# WizFiShield.net
KiCad netlist of a schematic drawn in EAGLE
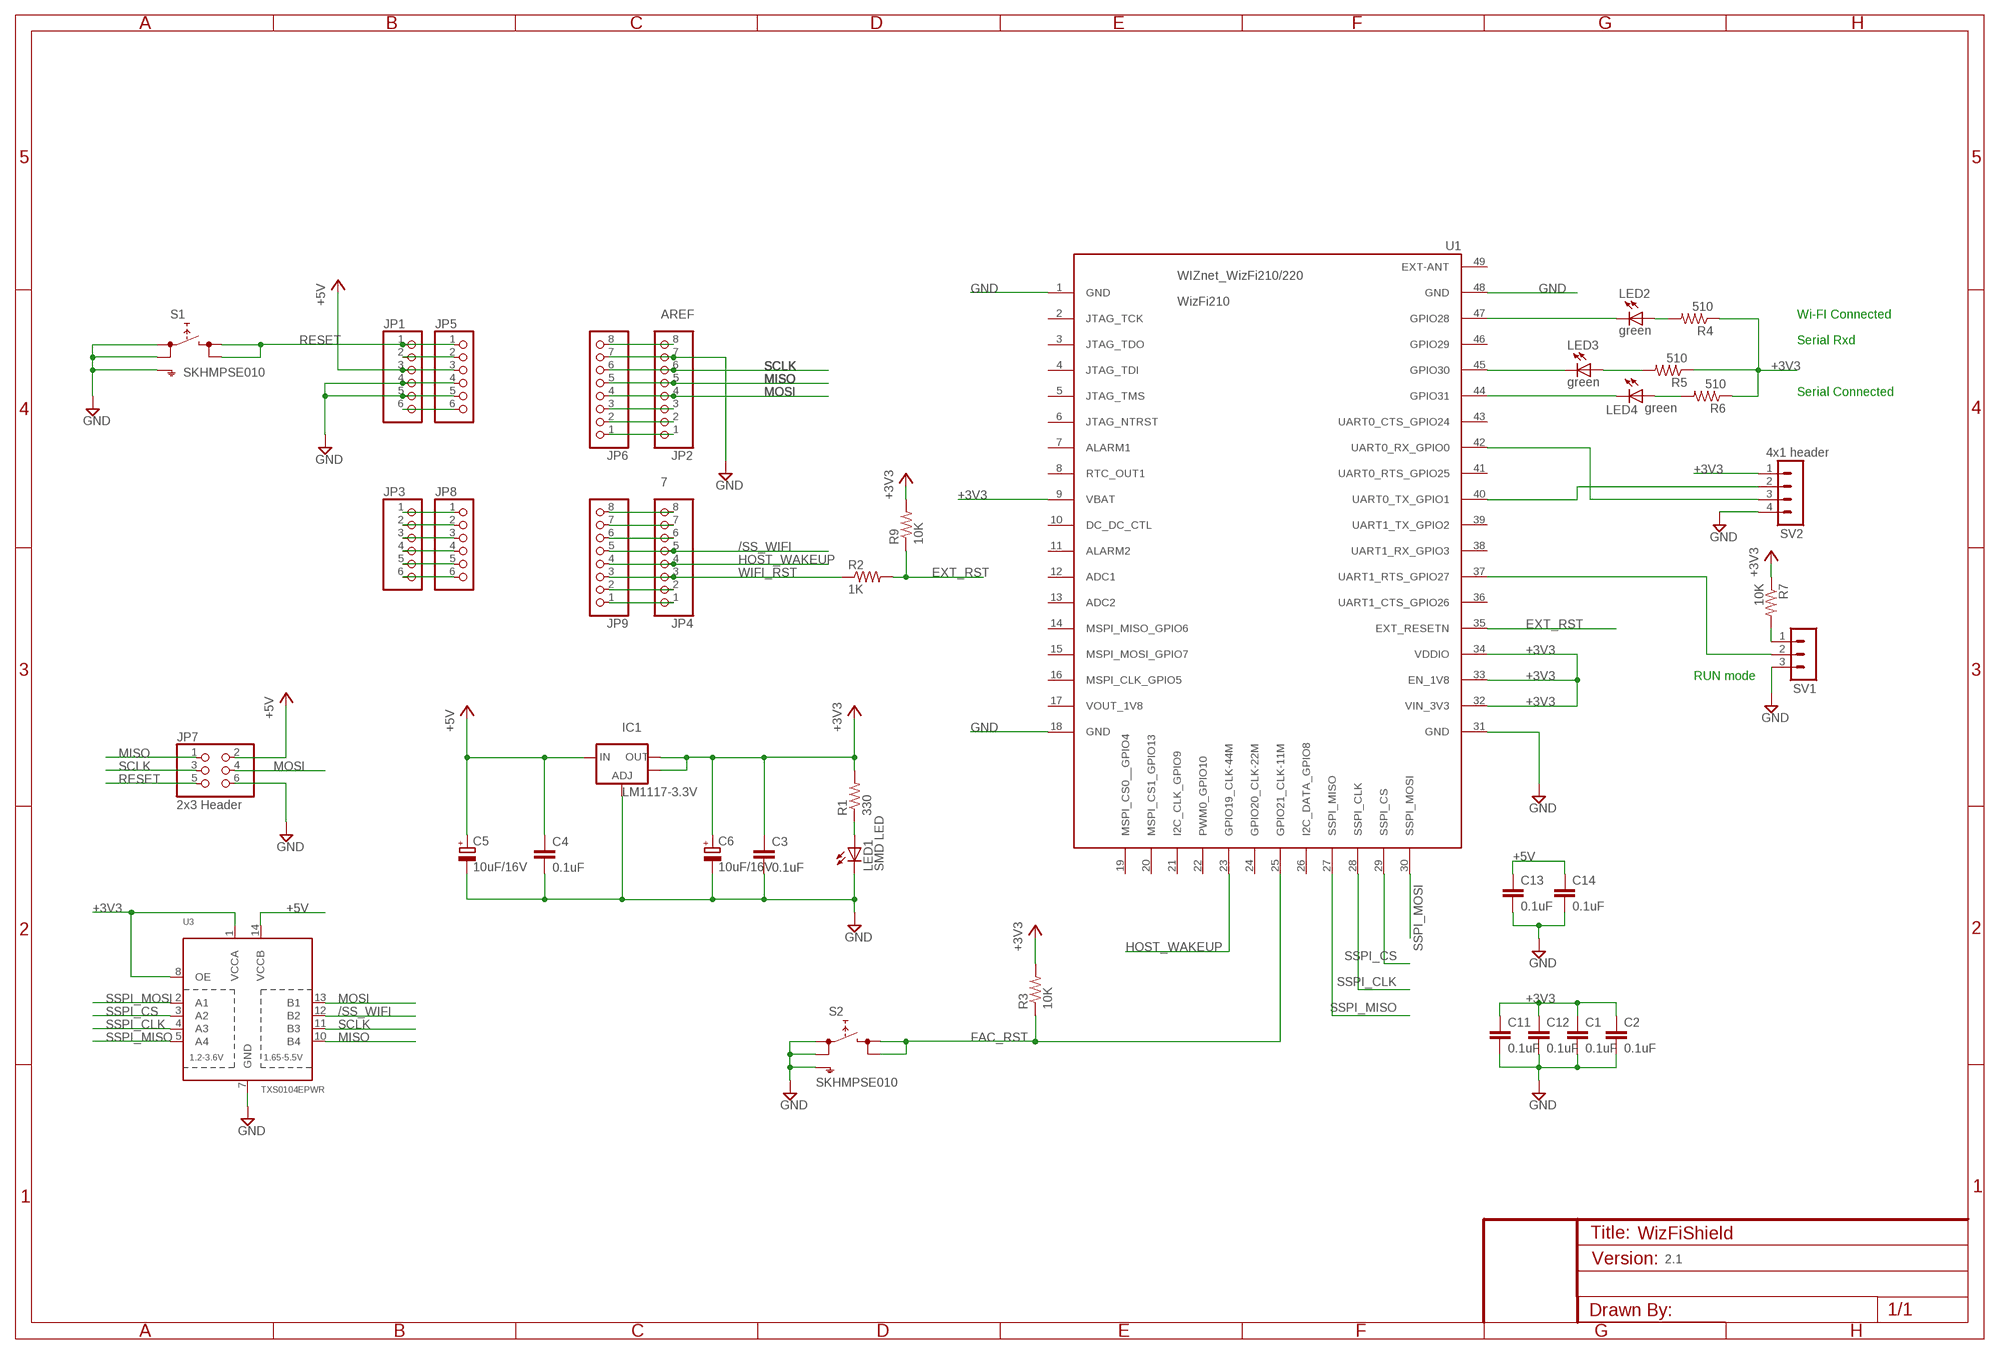
[diagram p0: schematic, sheet 1]

(export (version "E")
  (design (tool "Eeschema 10.0.6"))
  (components
    (comp (ref "C1")
      (value "0.1uF")
      (footprint "eagle-import:C0603")
      (libsource (lib "eagle-import") (part "C-EUC0603"))
    )
    (comp (ref "C2")
      (value "0.1uF")
      (footprint "eagle-import:C0603")
      (libsource (lib "eagle-import") (part "C-EUC0603"))
    )
    (comp (ref "C3")
      (value "0.1uF")
      (footprint "eagle-import:C0603")
      (libsource (lib "eagle-import") (part "C-EUC0603"))
    )
    (comp (ref "C4")
      (value "0.1uF")
      (footprint "eagle-import:C0603")
      (libsource (lib "eagle-import") (part "C-EUC0603"))
    )
    (comp (ref "C5")
      (value "10uF/16V")
      (footprint "eagle-import:CT3216")
      (libsource (lib "eagle-import") (part "CPOL-EUCT3216"))
    )
    (comp (ref "C6")
      (value "10uF/16V")
      (footprint "eagle-import:CT3216")
      (libsource (lib "eagle-import") (part "CPOL-EUCT3216"))
    )
    (comp (ref "C11")
      (value "0.1uF")
      (footprint "eagle-import:C0603")
      (libsource (lib "eagle-import") (part "C-EUC0603"))
    )
    (comp (ref "C12")
      (value "0.1uF")
      (footprint "eagle-import:C0603")
      (libsource (lib "eagle-import") (part "C-EUC0603"))
    )
    (comp (ref "C13")
      (value "0.1uF")
      (footprint "eagle-import:C0603")
      (libsource (lib "eagle-import") (part "C-EUC0603"))
    )
    (comp (ref "C14")
      (value "0.1uF")
      (footprint "eagle-import:C0603")
      (libsource (lib "eagle-import") (part "C-EUC0603"))
    )
    (comp (ref "IC1")
      (value "LM1117-3.3V")
      (footprint "eagle-import:SOT223")
      (libsource (lib "eagle-import") (part "V_REG_LM1117SOT223"))
    )
    (comp (ref "JP1")
      (value "PINHD-1X6")
      (footprint "eagle-import:1X06")
      (libsource (lib "eagle-import") (part "PINHD-1X6"))
    )
    (comp (ref "JP2")
      (value "PINHD-1X8")
      (footprint "eagle-import:1X08")
      (libsource (lib "eagle-import") (part "PINHD-1X8"))
    )
    (comp (ref "JP3")
      (value "PINHD-1X6")
      (footprint "eagle-import:1X06")
      (libsource (lib "eagle-import") (part "PINHD-1X6"))
    )
    (comp (ref "JP4")
      (value "PINHD-1X8")
      (footprint "eagle-import:1X08")
      (libsource (lib "eagle-import") (part "PINHD-1X8"))
    )
    (comp (ref "JP5")
      (value "PINHD-1X6")
      (footprint "eagle-import:1X06")
      (libsource (lib "eagle-import") (part "PINHD-1X6"))
    )
    (comp (ref "JP6")
      (value "PINHD-1X8")
      (footprint "eagle-import:1X08")
      (libsource (lib "eagle-import") (part "PINHD-1X8"))
    )
    (comp (ref "JP7")
      (value "2x3 Header")
      (footprint "eagle-import:2X03")
      (libsource (lib "eagle-import") (part "PINHD-2X3"))
    )
    (comp (ref "JP8")
      (value "PINHD-1X6")
      (footprint "eagle-import:1X06")
      (libsource (lib "eagle-import") (part "PINHD-1X6"))
    )
    (comp (ref "JP9")
      (value "PINHD-1X8")
      (footprint "eagle-import:1X08")
      (libsource (lib "eagle-import") (part "PINHD-1X8"))
    )
    (comp (ref "LED1")
      (value "SMD LED")
      (footprint "eagle-import:CHIP-LED0805")
      (libsource (lib "eagle-import") (part "led_LEDCHIP-LED0805"))
    )
    (comp (ref "LED2")
      (value "green")
      (footprint "eagle-import:CHIP-LED0805")
      (libsource (lib "eagle-import") (part "LEDCHIP-LED0805"))
    )
    (comp (ref "LED3")
      (value "green")
      (footprint "eagle-import:CHIP-LED0805")
      (libsource (lib "eagle-import") (part "LEDCHIP-LED0805"))
    )
    (comp (ref "LED4")
      (value "green")
      (footprint "eagle-import:CHIP-LED0805")
      (libsource (lib "eagle-import") (part "LEDCHIP-LED0805"))
    )
    (comp (ref "R1")
      (value "330")
      (footprint "eagle-import:R0805")
      (libsource (lib "eagle-import") (part "R-US_R0805"))
    )
    (comp (ref "R2")
      (value "1K")
      (footprint "eagle-import:0603-RES")
      (libsource (lib "eagle-import") (part "RESISTOR0603-RES"))
    )
    (comp (ref "R3")
      (value "10K")
      (footprint "eagle-import:0603-RES")
      (libsource (lib "eagle-import") (part "RESISTOR0603-RES"))
    )
    (comp (ref "R4")
      (value "510")
      (footprint "eagle-import:0603-RES")
      (libsource (lib "eagle-import") (part "RESISTOR0603-RES"))
    )
    (comp (ref "R5")
      (value "510")
      (footprint "eagle-import:0603-RES")
      (libsource (lib "eagle-import") (part "RESISTOR0603-RES"))
    )
    (comp (ref "R6")
      (value "510")
      (footprint "eagle-import:0603-RES")
      (libsource (lib "eagle-import") (part "RESISTOR0603-RES"))
    )
    (comp (ref "R7")
      (value "10K")
      (footprint "eagle-import:0603-RES")
      (libsource (lib "eagle-import") (part "RESISTOR0603-RES"))
    )
    (comp (ref "R9")
      (value "10K")
      (footprint "eagle-import:0603-RES")
      (libsource (lib "eagle-import") (part "RESISTOR0603-RES"))
    )
    (comp (ref "S1")
      (value "SKHMPSE010")
      (footprint "eagle-import:SKHMPXE010")
      (libsource (lib "eagle-import") (part "SKHMPE010S"))
    )
    (comp (ref "S2")
      (value "SKHMPSE010")
      (footprint "eagle-import:SKHMPXE010")
      (libsource (lib "eagle-import") (part "SKHMPE010S"))
    )
    (comp (ref "SV1")
      (value "MA03-1")
      (footprint "eagle-import:MA03-1")
      (libsource (lib "eagle-import") (part "MA03-1"))
    )
    (comp (ref "SV2")
      (value "4x1 header")
      (footprint "eagle-import:MA04-1")
      (libsource (lib "eagle-import") (part "MA04-1"))
    )
    (comp (ref "U1")
      (value "WizFi210")
      (footprint "eagle-import:WIZFI210_220")
      (libsource (lib "eagle-import") (part "WIZFI210/220"))
    )
    (comp (ref "U3")
      (value "TXS0104EPWR")
      (footprint "eagle-import:TSSOP14")
      (libsource (lib "eagle-import") (part "TXB0104PWR"))
    )
  )
  (nets
    (net (code "1") (name "+3V3") (class "Default")
      (node (ref "C1") (pin "1") (pinfunction "1_1") (pintype "passive"))
      (node (ref "C11") (pin "1") (pinfunction "1_1") (pintype "passive"))
      (node (ref "C12") (pin "1") (pinfunction "1_1") (pintype "passive"))
      (node (ref "C2") (pin "1") (pinfunction "1_1") (pintype "passive"))
      (node (ref "C3") (pin "1") (pinfunction "1_1") (pintype "passive"))
      (node (ref "C6") (pin "+") (pinfunction "+_+") (pintype "passive"))
      (node (ref "IC1") (pin "2") (pinfunction "OUT_2") (pintype "output"))
      (node (ref "IC1") (pin "4") (pinfunction "OUT_4") (pintype "output"))
      (node (ref "R1") (pin "2") (pinfunction "2_2") (pintype "passive"))
      (node (ref "R3") (pin "2") (pinfunction "2_2") (pintype "passive"))
      (node (ref "R4") (pin "1") (pinfunction "1_1") (pintype "passive"))
      (node (ref "R5") (pin "1") (pinfunction "1_1") (pintype "passive"))
      (node (ref "R6") (pin "1") (pinfunction "1_1") (pintype "passive"))
      (node (ref "R7") (pin "1") (pinfunction "1_1") (pintype "passive"))
      (node (ref "R9") (pin "2") (pinfunction "2_2") (pintype "passive"))
      (node (ref "SV2") (pin "1") (pinfunction "1_1") (pintype "passive"))
      (node (ref "U1") (pin "32") (pinfunction "VIN_3V3_32") (pintype "power_in"))
      (node (ref "U1") (pin "33") (pinfunction "EN_1V8_33") (pintype "input"))
      (node (ref "U1") (pin "34") (pinfunction "VDDIO_34") (pintype "power_in"))
      (node (ref "U1") (pin "9") (pinfunction "VBAT_9") (pintype "power_in"))
      (node (ref "U3") (pin "1") (pinfunction "VCCA_1") (pintype "bidirectional"))
      (node (ref "U3") (pin "8") (pinfunction "OE_8") (pintype "bidirectional"))
    )
    (net (code "2") (name "+5V") (class "Default")
      (node (ref "C13") (pin "1") (pinfunction "1_1") (pintype "passive"))
      (node (ref "C14") (pin "1") (pinfunction "1_1") (pintype "passive"))
      (node (ref "C4") (pin "1") (pinfunction "1_1") (pintype "passive"))
      (node (ref "C5") (pin "+") (pinfunction "+_+") (pintype "passive"))
      (node (ref "IC1") (pin "3") (pinfunction "IN_3") (pintype "input"))
      (node (ref "JP1") (pin "3") (pinfunction "3_3") (pintype "passive"))
      (node (ref "JP5") (pin "3") (pinfunction "3_3") (pintype "passive"))
      (node (ref "JP7") (pin "2") (pinfunction "2_2") (pintype "passive"))
      (node (ref "U3") (pin "14") (pinfunction "VCCB_14") (pintype "bidirectional"))
    )
    (net (code "3") (name "/EXT_RST") (class "Default")
      (node (ref "R2") (pin "2") (pinfunction "2_2") (pintype "passive"))
      (node (ref "R9") (pin "1") (pinfunction "1_1") (pintype "passive"))
      (node (ref "U1") (pin "35") (pinfunction "EXT_RESETN_35") (pintype "bidirectional"))
    )
    (net (code "4") (name "/FAC_RST") (class "Default")
      (node (ref "R3") (pin "1") (pinfunction "1_1") (pintype "passive"))
      (node (ref "S2") (pin "3") (pinfunction "2.1_3") (pintype "passive"))
      (node (ref "S2") (pin "4") (pinfunction "2.2_4") (pintype "passive"))
      (node (ref "U1") (pin "25") (pinfunction "GPIO21_CLK-11M_25") (pintype "input"))
    )
    (net (code "5") (name "/HOST_WAKEUP") (class "Default")
      (node (ref "JP4") (pin "4") (pinfunction "4_4") (pintype "passive"))
      (node (ref "JP9") (pin "4") (pinfunction "4_4") (pintype "passive"))
      (node (ref "U1") (pin "23") (pinfunction "GPIO19_CLK-44M_23") (pintype "input"))
    )
    (net (code "6") (name "/MISO") (class "Default")
      (node (ref "JP2") (pin "5") (pinfunction "5_5") (pintype "passive"))
      (node (ref "JP6") (pin "5") (pinfunction "5_5") (pintype "passive"))
      (node (ref "JP7") (pin "1") (pinfunction "1_1") (pintype "passive"))
      (node (ref "U3") (pin "10") (pinfunction "B4_10") (pintype "bidirectional"))
    )
    (net (code "7") (name "/MOSI") (class "Default")
      (node (ref "JP2") (pin "4") (pinfunction "4_4") (pintype "passive"))
      (node (ref "JP6") (pin "4") (pinfunction "4_4") (pintype "passive"))
      (node (ref "JP7") (pin "4") (pinfunction "4_4") (pintype "passive"))
      (node (ref "U3") (pin "13") (pinfunction "B1_13") (pintype "bidirectional"))
    )
    (net (code "8") (name "/RESET") (class "Default")
      (node (ref "JP1") (pin "1") (pinfunction "1_1") (pintype "passive"))
      (node (ref "JP5") (pin "1") (pinfunction "1_1") (pintype "passive"))
      (node (ref "JP7") (pin "5") (pinfunction "5_5") (pintype "passive"))
      (node (ref "S1") (pin "3") (pinfunction "2.1_3") (pintype "passive"))
      (node (ref "S1") (pin "4") (pinfunction "2.2_4") (pintype "passive"))
    )
    (net (code "9") (name "/SCLK") (class "Default")
      (node (ref "JP2") (pin "6") (pinfunction "6_6") (pintype "passive"))
      (node (ref "JP6") (pin "6") (pinfunction "6_6") (pintype "passive"))
      (node (ref "JP7") (pin "3") (pinfunction "3_3") (pintype "passive"))
      (node (ref "U3") (pin "11") (pinfunction "B3_11") (pintype "bidirectional"))
    )
    (net (code "10") (name "/SSPI_CLK") (class "Default")
      (node (ref "U1") (pin "28") (pinfunction "SSPI_CLK_28") (pintype "input"))
      (node (ref "U3") (pin "4") (pinfunction "A3_4") (pintype "bidirectional"))
    )
    (net (code "11") (name "/SSPI_CS") (class "Default")
      (node (ref "U1") (pin "29") (pinfunction "SSPI_CS_29") (pintype "input"))
      (node (ref "U3") (pin "3") (pinfunction "A2_3") (pintype "bidirectional"))
    )
    (net (code "12") (name "/SSPI_MISO") (class "Default")
      (node (ref "U1") (pin "27") (pinfunction "SSPI_MISO_27") (pintype "output"))
      (node (ref "U3") (pin "5") (pinfunction "A4_5") (pintype "bidirectional"))
    )
    (net (code "13") (name "/SSPI_MOSI") (class "Default")
      (node (ref "U1") (pin "30") (pinfunction "SSPI_MOSI_30") (pintype "input"))
      (node (ref "U3") (pin "2") (pinfunction "A1_2") (pintype "bidirectional"))
    )
    (net (code "14") (name "/WIFI_RST") (class "Default")
      (node (ref "JP4") (pin "3") (pinfunction "3_3") (pintype "passive"))
      (node (ref "JP9") (pin "3") (pinfunction "3_3") (pintype "passive"))
      (node (ref "R2") (pin "1") (pinfunction "1_1") (pintype "passive"))
    )
    (net (code "15") (name "/{slash}SS_WIFI") (class "Default")
      (node (ref "JP4") (pin "5") (pinfunction "5_5") (pintype "passive"))
      (node (ref "JP9") (pin "5") (pinfunction "5_5") (pintype "passive"))
      (node (ref "U3") (pin "12") (pinfunction "B2_12") (pintype "bidirectional"))
    )
    (net (code "16") (name "GND") (class "Default")
      (node (ref "C1") (pin "2") (pinfunction "2_2") (pintype "passive"))
      (node (ref "C11") (pin "2") (pinfunction "2_2") (pintype "passive"))
      (node (ref "C12") (pin "2") (pinfunction "2_2") (pintype "passive"))
      (node (ref "C13") (pin "2") (pinfunction "2_2") (pintype "passive"))
      (node (ref "C14") (pin "2") (pinfunction "2_2") (pintype "passive"))
      (node (ref "C2") (pin "2") (pinfunction "2_2") (pintype "passive"))
      (node (ref "C3") (pin "2") (pinfunction "2_2") (pintype "passive"))
      (node (ref "C4") (pin "2") (pinfunction "2_2") (pintype "passive"))
      (node (ref "C5") (pin "-") (pinfunction "-_-") (pintype "passive"))
      (node (ref "C6") (pin "-") (pinfunction "-_-") (pintype "passive"))
      (node (ref "IC1") (pin "1") (pinfunction "ADJ_1") (pintype "input"))
      (node (ref "JP1") (pin "4") (pinfunction "4_4") (pintype "passive"))
      (node (ref "JP1") (pin "5") (pinfunction "5_5") (pintype "passive"))
      (node (ref "JP2") (pin "7") (pinfunction "7_7") (pintype "passive"))
      (node (ref "JP5") (pin "4") (pinfunction "4_4") (pintype "passive"))
      (node (ref "JP5") (pin "5") (pinfunction "5_5") (pintype "passive"))
      (node (ref "JP6") (pin "7") (pinfunction "7_7") (pintype "passive"))
      (node (ref "JP7") (pin "6") (pinfunction "6_6") (pintype "passive"))
      (node (ref "LED1") (pin "C") (pinfunction "C_C") (pintype "passive"))
      (node (ref "S1") (pin "1") (pinfunction "1.1_1") (pintype "passive"))
      (node (ref "S1") (pin "2") (pinfunction "1.2_2") (pintype "passive"))
      (node (ref "S1") (pin "5") (pinfunction "SH_5") (pintype "passive"))
      (node (ref "S2") (pin "1") (pinfunction "1.1_1") (pintype "passive"))
      (node (ref "S2") (pin "2") (pinfunction "1.2_2") (pintype "passive"))
      (node (ref "S2") (pin "5") (pinfunction "SH_5") (pintype "passive"))
      (node (ref "SV1") (pin "3") (pinfunction "3_3") (pintype "passive"))
      (node (ref "SV2") (pin "4") (pinfunction "4_4") (pintype "passive"))
      (node (ref "U1") (pin "1") (pinfunction "GND_1") (pintype "power_in"))
      (node (ref "U1") (pin "18") (pinfunction "GND_18") (pintype "power_in"))
      (node (ref "U1") (pin "31") (pinfunction "GND_31") (pintype "power_in"))
      (node (ref "U1") (pin "48") (pinfunction "GND_48") (pintype "power_in"))
      (node (ref "U3") (pin "7") (pinfunction "GND_7") (pintype "bidirectional"))
    )
    (net (code "17") (name "Net-(JP1-Pad2)") (class "Default")
      (node (ref "JP1") (pin "2") (pinfunction "2_2") (pintype "passive"))
      (node (ref "JP5") (pin "2") (pinfunction "2_2") (pintype "passive"))
    )
    (net (code "18") (name "Net-(JP1-Pad6)") (class "Default")
      (node (ref "JP1") (pin "6") (pinfunction "6_6") (pintype "passive"))
      (node (ref "JP5") (pin "6") (pinfunction "6_6") (pintype "passive"))
    )
    (net (code "19") (name "Net-(JP2-Pad1)") (class "Default")
      (node (ref "JP2") (pin "1") (pinfunction "1_1") (pintype "passive"))
      (node (ref "JP6") (pin "1") (pinfunction "1_1") (pintype "passive"))
    )
    (net (code "20") (name "Net-(JP2-Pad2)") (class "Default")
      (node (ref "JP2") (pin "2") (pinfunction "2_2") (pintype "passive"))
      (node (ref "JP6") (pin "2") (pinfunction "2_2") (pintype "passive"))
    )
    (net (code "21") (name "Net-(JP2-Pad3)") (class "Default")
      (node (ref "JP2") (pin "3") (pinfunction "3_3") (pintype "passive"))
      (node (ref "JP6") (pin "3") (pinfunction "3_3") (pintype "passive"))
    )
    (net (code "22") (name "Net-(JP2-Pad8)") (class "Default")
      (node (ref "JP2") (pin "8") (pinfunction "8_8") (pintype "passive"))
      (node (ref "JP6") (pin "8") (pinfunction "8_8") (pintype "passive"))
    )
    (net (code "23") (name "Net-(JP3-Pad1)") (class "Default")
      (node (ref "JP3") (pin "1") (pinfunction "1_1") (pintype "passive"))
      (node (ref "JP8") (pin "1") (pinfunction "1_1") (pintype "passive"))
    )
    (net (code "24") (name "Net-(JP3-Pad2)") (class "Default")
      (node (ref "JP3") (pin "2") (pinfunction "2_2") (pintype "passive"))
      (node (ref "JP8") (pin "2") (pinfunction "2_2") (pintype "passive"))
    )
    (net (code "25") (name "Net-(JP3-Pad3)") (class "Default")
      (node (ref "JP3") (pin "3") (pinfunction "3_3") (pintype "passive"))
      (node (ref "JP8") (pin "3") (pinfunction "3_3") (pintype "passive"))
    )
    (net (code "26") (name "Net-(JP3-Pad4)") (class "Default")
      (node (ref "JP3") (pin "4") (pinfunction "4_4") (pintype "passive"))
      (node (ref "JP8") (pin "4") (pinfunction "4_4") (pintype "passive"))
    )
    (net (code "27") (name "Net-(JP3-Pad5)") (class "Default")
      (node (ref "JP3") (pin "5") (pinfunction "5_5") (pintype "passive"))
      (node (ref "JP8") (pin "5") (pinfunction "5_5") (pintype "passive"))
    )
    (net (code "28") (name "Net-(JP3-Pad6)") (class "Default")
      (node (ref "JP3") (pin "6") (pinfunction "6_6") (pintype "passive"))
      (node (ref "JP8") (pin "6") (pinfunction "6_6") (pintype "passive"))
    )
    (net (code "29") (name "Net-(JP4-Pad1)") (class "Default")
      (node (ref "JP4") (pin "1") (pinfunction "1_1") (pintype "passive"))
      (node (ref "JP9") (pin "1") (pinfunction "1_1") (pintype "passive"))
    )
    (net (code "30") (name "Net-(JP4-Pad2)") (class "Default")
      (node (ref "JP4") (pin "2") (pinfunction "2_2") (pintype "passive"))
      (node (ref "JP9") (pin "2") (pinfunction "2_2") (pintype "passive"))
    )
    (net (code "31") (name "Net-(JP4-Pad6)") (class "Default")
      (node (ref "JP4") (pin "6") (pinfunction "6_6") (pintype "passive"))
      (node (ref "JP9") (pin "6") (pinfunction "6_6") (pintype "passive"))
    )
    (net (code "32") (name "Net-(JP4-Pad7)") (class "Default")
      (node (ref "JP4") (pin "7") (pinfunction "7_7") (pintype "passive"))
      (node (ref "JP9") (pin "7") (pinfunction "7_7") (pintype "passive"))
    )
    (net (code "33") (name "Net-(JP4-Pad8)") (class "Default")
      (node (ref "JP4") (pin "8") (pinfunction "8_8") (pintype "passive"))
      (node (ref "JP9") (pin "8") (pinfunction "8_8") (pintype "passive"))
    )
    (net (code "34") (name "Net-(LED1-PadA)") (class "Default")
      (node (ref "LED1") (pin "A") (pinfunction "A_A") (pintype "passive"))
      (node (ref "R1") (pin "1") (pinfunction "1_1") (pintype "passive"))
    )
    (net (code "35") (name "Net-(LED2-PadA)") (class "Default")
      (node (ref "LED2") (pin "A") (pinfunction "A_A") (pintype "passive"))
      (node (ref "R4") (pin "2") (pinfunction "2_2") (pintype "passive"))
    )
    (net (code "36") (name "Net-(LED3-PadA)") (class "Default")
      (node (ref "LED3") (pin "A") (pinfunction "A_A") (pintype "passive"))
      (node (ref "R5") (pin "2") (pinfunction "2_2") (pintype "passive"))
    )
    (net (code "37") (name "Net-(LED4-PadA)") (class "Default")
      (node (ref "LED4") (pin "A") (pinfunction "A_A") (pintype "passive"))
      (node (ref "R6") (pin "2") (pinfunction "2_2") (pintype "passive"))
    )
    (net (code "38") (name "Net-(R7-Pad2)") (class "Default")
      (node (ref "R7") (pin "2") (pinfunction "2_2") (pintype "passive"))
      (node (ref "SV1") (pin "1") (pinfunction "1_1") (pintype "passive"))
    )
    (net (code "39") (name "Net-(U1-GPIO28)") (class "Default")
      (node (ref "LED2") (pin "C") (pinfunction "C_C") (pintype "passive"))
      (node (ref "U1") (pin "47") (pinfunction "GPIO28_47") (pintype "bidirectional"))
    )
    (net (code "40") (name "Net-(U1-GPIO30)") (class "Default")
      (node (ref "LED3") (pin "C") (pinfunction "C_C") (pintype "passive"))
      (node (ref "U1") (pin "45") (pinfunction "GPIO30_45") (pintype "bidirectional"))
    )
    (net (code "41") (name "Net-(U1-GPIO31)") (class "Default")
      (node (ref "LED4") (pin "C") (pinfunction "C_C") (pintype "passive"))
      (node (ref "U1") (pin "44") (pinfunction "GPIO31_44") (pintype "bidirectional"))
    )
    (net (code "42") (name "Net-(U1-UART0_RX_GPIO0)") (class "Default")
      (node (ref "SV2") (pin "3") (pinfunction "3_3") (pintype "passive"))
      (node (ref "U1") (pin "42") (pinfunction "UART0_RX_GPIO0_42") (pintype "input"))
    )
    (net (code "43") (name "Net-(U1-UART0_TX_GPIO1)") (class "Default")
      (node (ref "SV2") (pin "2") (pinfunction "2_2") (pintype "passive"))
      (node (ref "U1") (pin "40") (pinfunction "UART0_TX_GPIO1_40") (pintype "output"))
    )
    (net (code "44") (name "Net-(U1-UART1_RTS_GPIO27)") (class "Default")
      (node (ref "SV1") (pin "2") (pinfunction "2_2") (pintype "passive"))
      (node (ref "U1") (pin "37") (pinfunction "UART1_RTS_GPIO27_37") (pintype "output"))
    )
    (net (code "45") (name "unconnected-(U1-ADC1-Pad12)") (class "Default")
      (node (ref "U1") (pin "12") (pinfunction "ADC1_12") (pintype "input"))
    )
    (net (code "46") (name "unconnected-(U1-ADC2-Pad13)") (class "Default")
      (node (ref "U1") (pin "13") (pinfunction "ADC2_13") (pintype "input"))
    )
    (net (code "47") (name "unconnected-(U1-ALARM1-Pad7)") (class "Default")
      (node (ref "U1") (pin "7") (pinfunction "ALARM1_7") (pintype "input"))
    )
    (net (code "48") (name "unconnected-(U1-ALARM2-Pad11)") (class "Default")
      (node (ref "U1") (pin "11") (pinfunction "ALARM2_11") (pintype "input"))
    )
    (net (code "49") (name "unconnected-(U1-DC_DC_CTL-Pad10)") (class "Default")
      (node (ref "U1") (pin "10") (pinfunction "DC_DC_CTL_10") (pintype "output"))
    )
    (net (code "50") (name "unconnected-(U1-EXT-ANT-Pad49)") (class "Default")
      (node (ref "U1") (pin "49") (pinfunction "EXT-ANT_49") (pintype "bidirectional"))
    )
    (net (code "51") (name "unconnected-(U1-GPIO20_CLK-22M-Pad24)") (class "Default")
      (node (ref "U1") (pin "24") (pinfunction "GPIO20_CLK-22M_24") (pintype "input"))
    )
    (net (code "52") (name "unconnected-(U1-GPIO29-Pad46)") (class "Default")
      (node (ref "U1") (pin "46") (pinfunction "GPIO29_46") (pintype "bidirectional"))
    )
    (net (code "53") (name "unconnected-(U1-I2C_CLK_GPIO9-Pad21)") (class "Default")
      (node (ref "U1") (pin "21") (pinfunction "I2C_CLK_GPIO9_21") (pintype "bidirectional"))
    )
    (net (code "54") (name "unconnected-(U1-I2C_DATA_GPIO8-Pad26)") (class "Default")
      (node (ref "U1") (pin "26") (pinfunction "I2C_DATA_GPIO8_26") (pintype "bidirectional"))
    )
    (net (code "55") (name "unconnected-(U1-JTAG_NTRST-Pad6)") (class "Default")
      (node (ref "U1") (pin "6") (pinfunction "JTAG_NTRST_6") (pintype "input"))
    )
    (net (code "56") (name "unconnected-(U1-JTAG_TCK-Pad2)") (class "Default")
      (node (ref "U1") (pin "2") (pinfunction "JTAG_TCK_2") (pintype "input"))
    )
    (net (code "57") (name "unconnected-(U1-JTAG_TDI-Pad4)") (class "Default")
      (node (ref "U1") (pin "4") (pinfunction "JTAG_TDI_4") (pintype "input"))
    )
    (net (code "58") (name "unconnected-(U1-JTAG_TDO-Pad3)") (class "Default")
      (node (ref "U1") (pin "3") (pinfunction "JTAG_TDO_3") (pintype "output"))
    )
    (net (code "59") (name "unconnected-(U1-JTAG_TMS-Pad5)") (class "Default")
      (node (ref "U1") (pin "5") (pinfunction "JTAG_TMS_5") (pintype "input"))
    )
    (net (code "60") (name "unconnected-(U1-MSPI_CLK_GPIO5-Pad16)") (class "Default")
      (node (ref "U1") (pin "16") (pinfunction "MSPI_CLK_GPIO5_16") (pintype "bidirectional"))
    )
    (net (code "61") (name "unconnected-(U1-MSPI_CS0__GPIO4-Pad19)") (class "Default")
      (node (ref "U1") (pin "19") (pinfunction "MSPI_CS0__GPIO4_19") (pintype "output"))
    )
    (net (code "62") (name "unconnected-(U1-MSPI_CS1_GPIO13-Pad20)") (class "Default")
      (node (ref "U1") (pin "20") (pinfunction "MSPI_CS1_GPIO13_20") (pintype "output"))
    )
    (net (code "63") (name "unconnected-(U1-MSPI_MISO_GPIO6-Pad14)") (class "Default")
      (node (ref "U1") (pin "14") (pinfunction "MSPI_MISO_GPIO6_14") (pintype "input"))
    )
    (net (code "64") (name "unconnected-(U1-MSPI_MOSI_GPIO7-Pad15)") (class "Default")
      (node (ref "U1") (pin "15") (pinfunction "MSPI_MOSI_GPIO7_15") (pintype "output"))
    )
    (net (code "65") (name "unconnected-(U1-PWM0_GPIO10-Pad22)") (class "Default")
      (node (ref "U1") (pin "22") (pinfunction "PWM0_GPIO10_22") (pintype "output"))
    )
    (net (code "66") (name "unconnected-(U1-RTC_OUT1-Pad8)") (class "Default")
      (node (ref "U1") (pin "8") (pinfunction "RTC_OUT1_8") (pintype "output"))
    )
    (net (code "67") (name "unconnected-(U1-UART0_CTS_GPIO24-Pad43)") (class "Default")
      (node (ref "U1") (pin "43") (pinfunction "UART0_CTS_GPIO24_43") (pintype "input"))
    )
    (net (code "68") (name "unconnected-(U1-UART0_RTS_GPIO25-Pad41)") (class "Default")
      (node (ref "U1") (pin "41") (pinfunction "UART0_RTS_GPIO25_41") (pintype "output"))
    )
    (net (code "69") (name "unconnected-(U1-UART1_CTS_GPIO26-Pad36)") (class "Default")
      (node (ref "U1") (pin "36") (pinfunction "UART1_CTS_GPIO26_36") (pintype "input"))
    )
    (net (code "70") (name "unconnected-(U1-UART1_RX_GPIO3-Pad38)") (class "Default")
      (node (ref "U1") (pin "38") (pinfunction "UART1_RX_GPIO3_38") (pintype "input"))
    )
    (net (code "71") (name "unconnected-(U1-UART1_TX_GPIO2-Pad39)") (class "Default")
      (node (ref "U1") (pin "39") (pinfunction "UART1_TX_GPIO2_39") (pintype "output"))
    )
    (net (code "72") (name "unconnected-(U1-VOUT_1V8-Pad17)") (class "Default")
      (node (ref "U1") (pin "17") (pinfunction "VOUT_1V8_17") (pintype "bidirectional"))
    )
  )
)
